# LipSync4_UI_Board_Alpha2.net
KiCad netlist of a schematic drawn in EAGLE
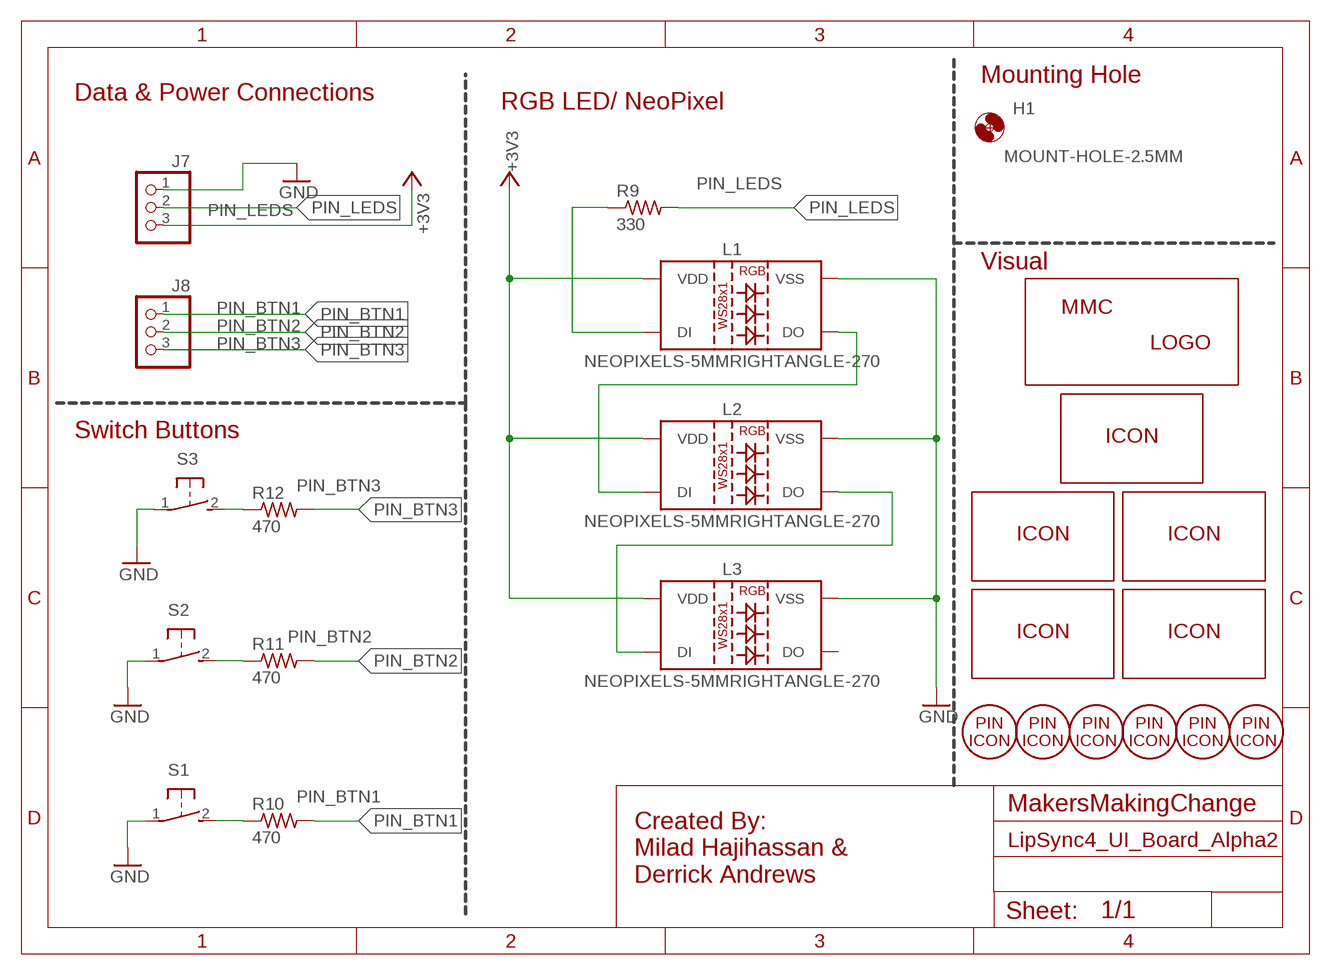
[diagram p0: schematic, sheet 1]

(export (version "E")
  (design (tool "Eeschema 10.0.6"))
  (components
    (comp (ref "H1")
      (value "MOUNT-HOLE-2.5MM")
      (footprint "eagle-import:HOLE-2.5MM")
      (libsource (lib "eagle-import") (part "MOUNT-HOLE-2.5MM"))
    )
    (comp (ref "J7")
      (value "HEADER_FEMALE-1X3-LONGER")
      (footprint "eagle-import:HEADER_FEMALE-1X03_LONGER")
      (libsource (lib "eagle-import") (part "HEADER_FEMALE-1X3-LONGER"))
    )
    (comp (ref "J8")
      (value "HEADER_FEMALE-1X3-LONGER")
      (footprint "eagle-import:HEADER_FEMALE-1X03_LONGER")
      (libsource (lib "eagle-import") (part "HEADER_FEMALE-1X3-LONGER"))
    )
    (comp (ref "L1")
      (value "NEOPIXELS-5MMRIGHTANGLE-270")
      (footprint "eagle-import:NEOPIXELS-RIGHTANGLE-270-5MM")
      (libsource (lib "eagle-import") (part "NEOPIXELS-5MMRIGHTANGLE-270"))
    )
    (comp (ref "L2")
      (value "NEOPIXELS-5MMRIGHTANGLE-270")
      (footprint "eagle-import:NEOPIXELS-RIGHTANGLE-270-5MM")
      (libsource (lib "eagle-import") (part "NEOPIXELS-5MMRIGHTANGLE-270"))
    )
    (comp (ref "L3")
      (value "NEOPIXELS-5MMRIGHTANGLE-270")
      (footprint "eagle-import:NEOPIXELS-RIGHTANGLE-270-5MM")
      (libsource (lib "eagle-import") (part "NEOPIXELS-5MMRIGHTANGLE-270"))
    )
    (comp (ref "LABEL_ALPHA2-BOTTOM")
      (value "MMC_ICON-ALPHA2")
      (footprint "eagle-import:ICON_ALPHA2")
      (libsource (lib "eagle-import") (part "MMC_ICON-ALPHA2"))
    )
    (comp (ref "LABEL_BUTTON")
      (value "MMC_ICON-BUTTON")
      (footprint "eagle-import:ICON_BUTTON")
      (libsource (lib "eagle-import") (part "MMC_ICON-BUTTON"))
    )
    (comp (ref "LABEL_ICON_PIN-DATA")
      (value "MMC_PIN-ICON-DATA")
      (footprint "eagle-import:PIN-ICON_DATA")
      (libsource (lib "eagle-import") (part "MMC_PIN-ICON-DATA"))
    )
    (comp (ref "LABEL_ICON_PIN-GND")
      (value "MMC_PIN-ICON-GND")
      (footprint "eagle-import:PIN-ICON_GND")
      (libsource (lib "eagle-import") (part "MMC_PIN-ICON-GND"))
    )
    (comp (ref "LABEL_ICON_PIN-VCC")
      (value "MMC_PIN-ICON-VCC")
      (footprint "eagle-import:PIN-ICON_VCC")
      (libsource (lib "eagle-import") (part "MMC_PIN-ICON-VCC"))
    )
    (comp (ref "LABEL_ICON_PIN1")
      (value "MMC_PIN-ICON-PIN1")
      (footprint "eagle-import:PIN-ICON_1")
      (libsource (lib "eagle-import") (part "MMC_PIN-ICON-PIN1"))
    )
    (comp (ref "LABEL_ICON_PIN2")
      (value "MMC_PIN-ICON-PIN2")
      (footprint "eagle-import:PIN-ICON_2")
      (libsource (lib "eagle-import") (part "MMC_PIN-ICON-PIN2"))
    )
    (comp (ref "LABEL_ICON_PIN3")
      (value "MMC_PIN-ICON-PIN3")
      (footprint "eagle-import:PIN-ICON_3")
      (libsource (lib "eagle-import") (part "MMC_PIN-ICON-PIN3"))
    )
    (comp (ref "LABEL_LED")
      (value "MMC_ICON-LED")
      (footprint "eagle-import:ICON_LED")
      (libsource (lib "eagle-import") (part "MMC_ICON-LED"))
    )
    (comp (ref "LABEL_LIPSYNC-BOTTOM")
      (value "MMC_ICON-LIPSYNC4")
      (footprint "eagle-import:ICON_LIPSYNC4")
      (libsource (lib "eagle-import") (part "MMC_ICON-LIPSYNC4"))
    )
    (comp (ref "LABEL_MMC-LOGO")
      (value "MMC_LOGO-SM")
      (footprint "eagle-import:MMC_SMALL_LOGO")
      (libsource (lib "eagle-import") (part "MMC_LOGO-SM"))
    )
    (comp (ref "LABE_UI-BOARD-BOTTOM")
      (value "MMC_ICON-UI-BOARD")
      (footprint "eagle-import:ICON_UI-BOARD")
      (libsource (lib "eagle-import") (part "MMC_ICON-UI-BOARD"))
    )
    (comp (ref "R9")
      (value "330")
      (footprint "eagle-import:RESISTOR_0204_5")
      (libsource (lib "eagle-import") (part "RESISTOR-US-0204/5"))
    )
    (comp (ref "R10")
      (value "470")
      (footprint "eagle-import:RESISTOR_0204_5")
      (libsource (lib "eagle-import") (part "RESISTOR-US-0204/5"))
    )
    (comp (ref "R11")
      (value "470")
      (footprint "eagle-import:RESISTOR_0204_5")
      (libsource (lib "eagle-import") (part "RESISTOR-US-0204/5"))
    )
    (comp (ref "R12")
      (value "470")
      (footprint "eagle-import:RESISTOR_0204_5")
      (libsource (lib "eagle-import") (part "RESISTOR-US-0204/5"))
    )
    (comp (ref "S1")
      (value "SWITCH_OMRON_RA-RA")
      (footprint "eagle-import:B3F-31XX")
      (libsource (lib "eagle-import") (part "SWITCH_OMRON_RA-RA"))
    )
    (comp (ref "S2")
      (value "SWITCH_OMRON_RA-RA")
      (footprint "eagle-import:B3F-31XX")
      (libsource (lib "eagle-import") (part "SWITCH_OMRON_RA-RA"))
    )
    (comp (ref "S3")
      (value "SWITCH_OMRON_RA-RA")
      (footprint "eagle-import:B3F-31XX")
      (libsource (lib "eagle-import") (part "SWITCH_OMRON_RA-RA"))
    )
  )
  (nets
    (net (code "1") (name "+3V3") (class "Default")
      (node (ref "J7") (pin "3") (pinfunction "3_3") (pintype "passive"))
      (node (ref "L1") (pin "P2") (pinfunction "VDD_P2") (pintype "bidirectional"))
      (node (ref "L2") (pin "P2") (pinfunction "VDD_P2") (pintype "bidirectional"))
      (node (ref "L3") (pin "P2") (pinfunction "VDD_P2") (pintype "bidirectional"))
    )
    (net (code "2") (name "GND") (class "Default")
      (node (ref "J7") (pin "1") (pinfunction "1_1") (pintype "passive"))
      (node (ref "L1") (pin "P3") (pinfunction "VSS_P3") (pintype "bidirectional"))
      (node (ref "L2") (pin "P3") (pinfunction "VSS_P3") (pintype "bidirectional"))
      (node (ref "L3") (pin "P3") (pinfunction "VSS_P3") (pintype "bidirectional"))
      (node (ref "S1") (pin "1") (pinfunction "1_1") (pintype "passive"))
      (node (ref "S2") (pin "1") (pinfunction "1_1") (pintype "passive"))
      (node (ref "S3") (pin "1") (pinfunction "1_1") (pintype "passive"))
    )
    (net (code "3") (name "Net-(L1-DI)") (class "Default")
      (node (ref "L1") (pin "P1") (pinfunction "DI_P1") (pintype "bidirectional"))
      (node (ref "R9") (pin "1") (pinfunction "1_1") (pintype "passive"))
    )
    (net (code "4") (name "Net-(L1-DO)") (class "Default")
      (node (ref "L1") (pin "P4") (pinfunction "DO_P4") (pintype "bidirectional"))
      (node (ref "L2") (pin "P1") (pinfunction "DI_P1") (pintype "bidirectional"))
    )
    (net (code "5") (name "Net-(L2-DO)") (class "Default")
      (node (ref "L2") (pin "P4") (pinfunction "DO_P4") (pintype "bidirectional"))
      (node (ref "L3") (pin "P1") (pinfunction "DI_P1") (pintype "bidirectional"))
    )
    (net (code "6") (name "Net-(R10-Pad1)") (class "Default")
      (node (ref "R10") (pin "1") (pinfunction "1_1") (pintype "passive"))
      (node (ref "S1") (pin "2") (pinfunction "2_2") (pintype "passive"))
    )
    (net (code "7") (name "Net-(R11-Pad1)") (class "Default")
      (node (ref "R11") (pin "1") (pinfunction "1_1") (pintype "passive"))
      (node (ref "S2") (pin "2") (pinfunction "2_2") (pintype "passive"))
    )
    (net (code "8") (name "Net-(R12-Pad1)") (class "Default")
      (node (ref "R12") (pin "1") (pinfunction "1_1") (pintype "passive"))
      (node (ref "S3") (pin "2") (pinfunction "2_2") (pintype "passive"))
    )
    (net (code "9") (name "PIN_BTN1") (class "Default")
      (node (ref "J8") (pin "1") (pinfunction "1_1") (pintype "passive"))
      (node (ref "R10") (pin "2") (pinfunction "2_2") (pintype "passive"))
    )
    (net (code "10") (name "PIN_BTN2") (class "Default")
      (node (ref "J8") (pin "2") (pinfunction "2_2") (pintype "passive"))
      (node (ref "R11") (pin "2") (pinfunction "2_2") (pintype "passive"))
    )
    (net (code "11") (name "PIN_BTN3") (class "Default")
      (node (ref "J8") (pin "3") (pinfunction "3_3") (pintype "passive"))
      (node (ref "R12") (pin "2") (pinfunction "2_2") (pintype "passive"))
    )
    (net (code "12") (name "PIN_LEDS") (class "Default")
      (node (ref "J7") (pin "2") (pinfunction "2_2") (pintype "passive"))
      (node (ref "R9") (pin "2") (pinfunction "2_2") (pintype "passive"))
    )
    (net (code "13") (name "unconnected-(L3-DO-PadP4)") (class "Default")
      (node (ref "L3") (pin "P4") (pinfunction "DO_P4") (pintype "bidirectional"))
    )
  )
)
